# TAM_UNO.net
KiCad netlist of a schematic drawn in EAGLE
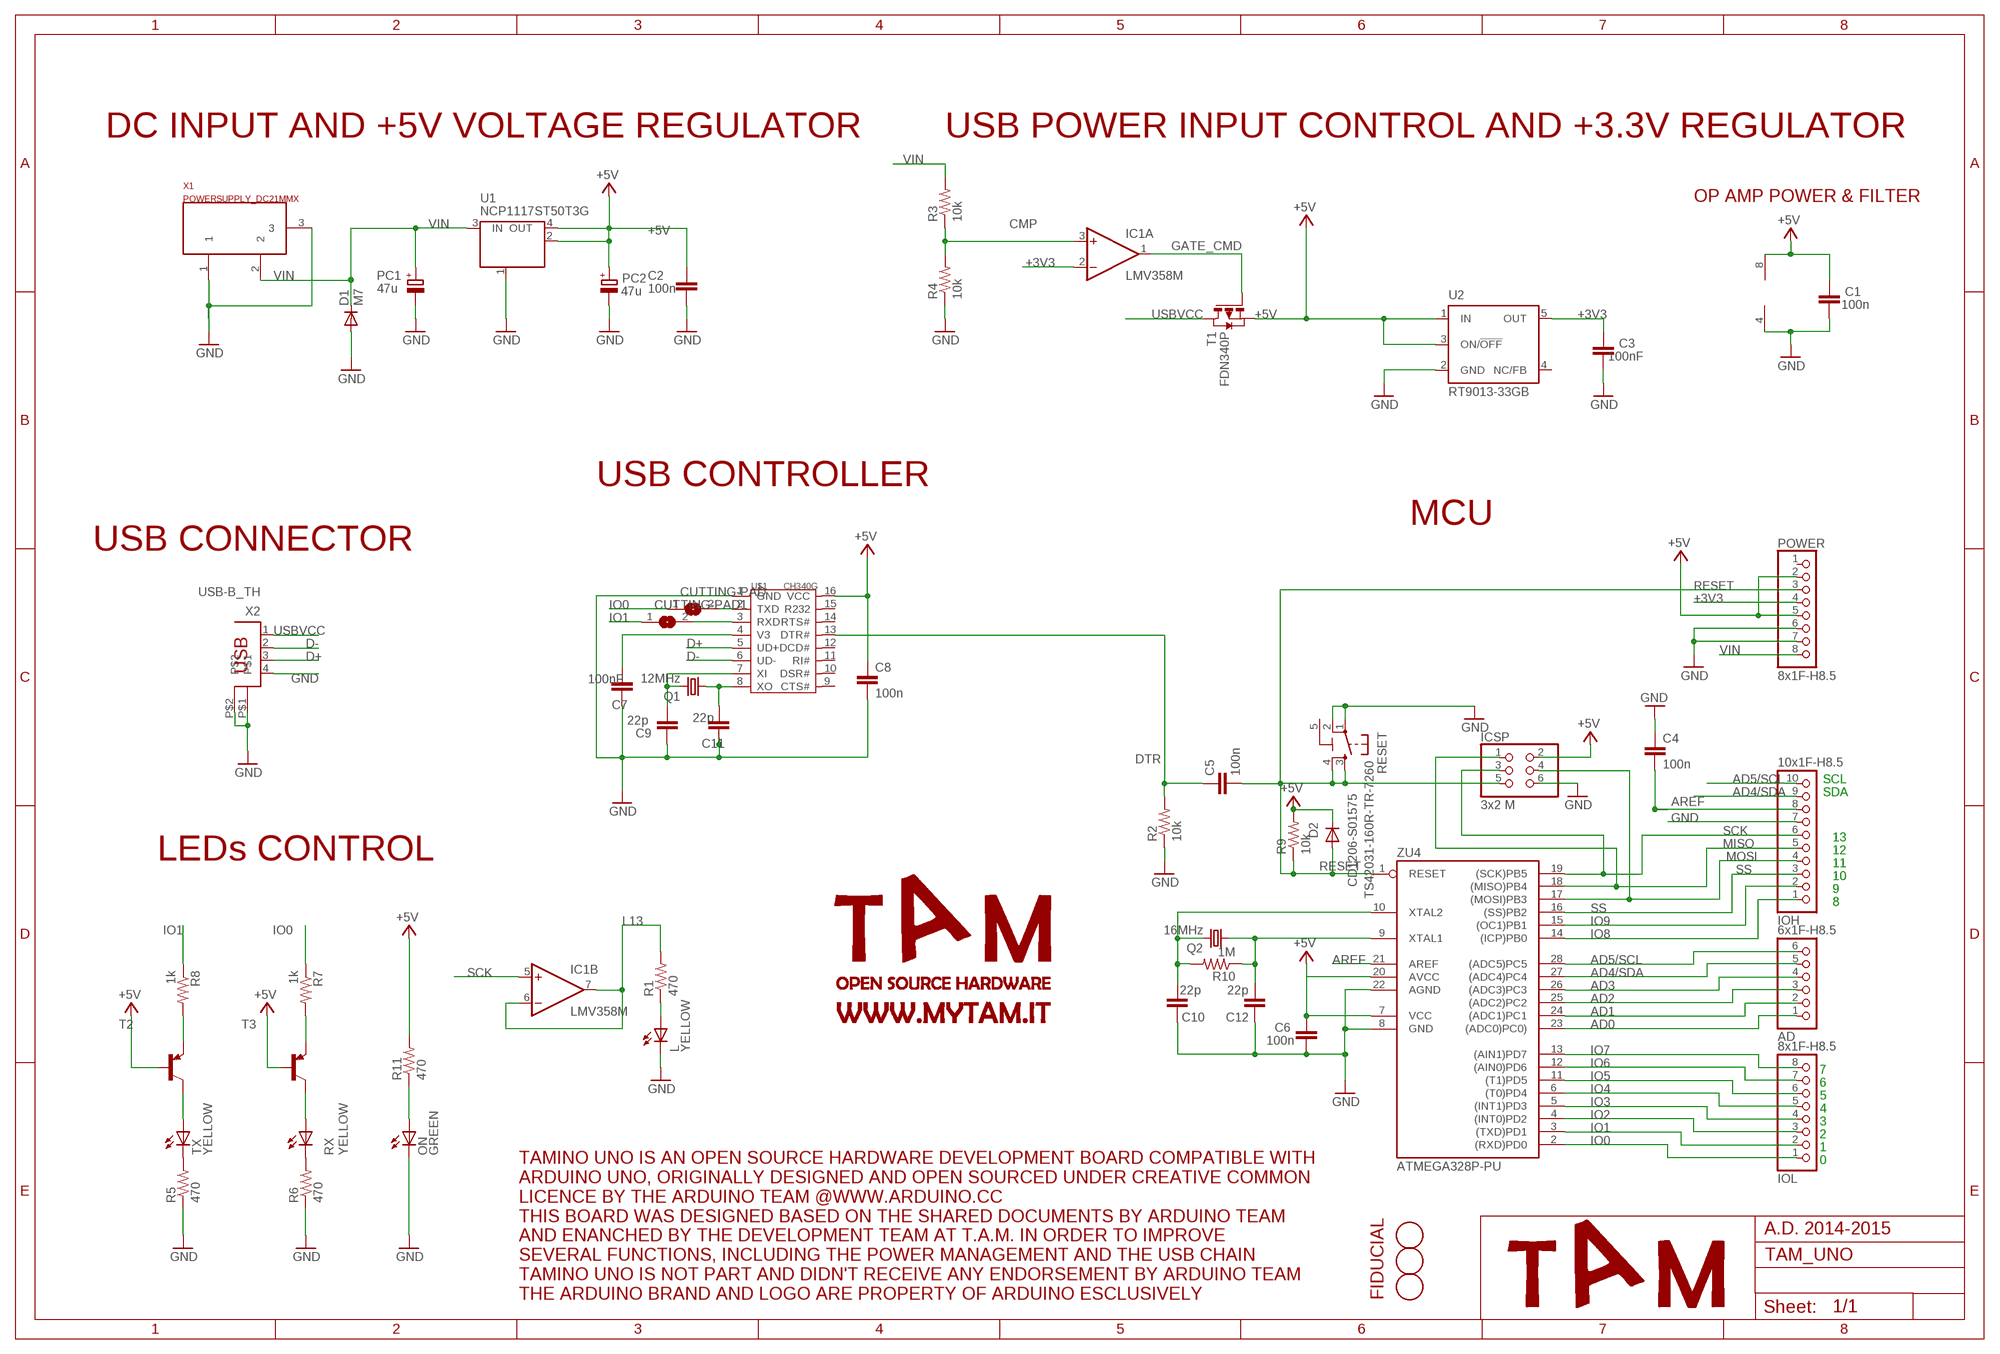
[diagram p0: schematic, sheet 1]

(export (version "E")
  (design (tool "Eeschema 10.0.6"))
  (components
    (comp (ref "AD")
      (value "6x1F-H8.5")
      (footprint "eagle-import:1X06")
      (libsource (lib "eagle-import") (part "PINHD-1X6"))
    )
    (comp (ref "C1")
      (value "100n")
      (footprint "eagle-import:C0603K")
      (libsource (lib "eagle-import") (part "C-EUC0603K"))
    )
    (comp (ref "C2")
      (value "100n")
      (footprint "eagle-import:C0603K")
      (libsource (lib "eagle-import") (part "C-EUC0603K"))
    )
    (comp (ref "C3")
      (value "100nF")
      (footprint "eagle-import:C0603K")
      (libsource (lib "eagle-import") (part "C-EUC0603K"))
    )
    (comp (ref "C4")
      (value "100n")
      (footprint "eagle-import:C0603K")
      (libsource (lib "eagle-import") (part "C-EUC0603K"))
    )
    (comp (ref "C5")
      (value "100n")
      (footprint "eagle-import:C0603K")
      (libsource (lib "eagle-import") (part "C-EUC0603K"))
    )
    (comp (ref "C6")
      (value "100n")
      (footprint "eagle-import:C0603K")
      (libsource (lib "eagle-import") (part "C-EUC0603K"))
    )
    (comp (ref "C7")
      (value "100nF")
      (footprint "eagle-import:C0603K")
      (libsource (lib "eagle-import") (part "C-EUC0603K"))
    )
    (comp (ref "C8")
      (value "100n")
      (footprint "eagle-import:C0603K")
      (libsource (lib "eagle-import") (part "C-EUC0603K"))
    )
    (comp (ref "C9")
      (value "22p")
      (footprint "eagle-import:C0603K")
      (libsource (lib "eagle-import") (part "C-EUC0603K"))
    )
    (comp (ref "C10")
      (value "22p")
      (footprint "eagle-import:C0603K")
      (libsource (lib "eagle-import") (part "C-EUC0603K"))
    )
    (comp (ref "C11")
      (value "22p")
      (footprint "eagle-import:C0603K")
      (libsource (lib "eagle-import") (part "C-EUC0603K"))
    )
    (comp (ref "C12")
      (value "22p")
      (footprint "eagle-import:C0603K")
      (libsource (lib "eagle-import") (part "C-EUC0603K"))
    )
    (comp (ref "CUTTING-PAD")
      (value "SJ")
      (footprint "eagle-import:SJ")
      (libsource (lib "eagle-import") (part "SJ"))
    )
    (comp (ref "CUTTING-PAD1")
      (value "SJ")
      (footprint "eagle-import:SJ")
      (libsource (lib "eagle-import") (part "SJ"))
    )
    (comp (ref "D1")
      (value "M7")
      (footprint "eagle-import:SMB")
      (libsource (lib "eagle-import") (part "DIODE-SMB"))
    )
    (comp (ref "D2")
      (value "CD1206-S01575")
      (footprint "eagle-import:MINIMELF")
      (libsource (lib "eagle-import") (part "DIODE-MINIMELF"))
    )
    (comp (ref "FD1")
      (value "FIDUCIALMOUNT")
      (footprint "eagle-import:FIDUCIA-MOUNT")
      (libsource (lib "eagle-import") (part "FIDUCIALMOUNT"))
    )
    (comp (ref "FD2")
      (value "FIDUCIALMOUNT")
      (footprint "eagle-import:FIDUCIA-MOUNT")
      (libsource (lib "eagle-import") (part "FIDUCIALMOUNT"))
    )
    (comp (ref "FD3")
      (value "FIDUCIALMOUNT")
      (footprint "eagle-import:FIDUCIA-MOUNT")
      (libsource (lib "eagle-import") (part "FIDUCIALMOUNT"))
    )
    (comp (ref "IC1")
      (value "LMV358M")
      (footprint "eagle-import:SO08")
      (libsource (lib "eagle-import") (part "LMV358?M"))
    )
    (comp (ref "ICSP")
      (value "3x2 M")
      (footprint "eagle-import:2X03")
      (libsource (lib "eagle-import") (part "PINHD-2X3"))
    )
    (comp (ref "IOH")
      (value "10x1F-H8.5")
      (footprint "eagle-import:1X10")
      (libsource (lib "eagle-import") (part "PINHD-1X10_ARD"))
    )
    (comp (ref "IOL")
      (value "8x1F-H8.5")
      (footprint "eagle-import:1X08")
      (libsource (lib "eagle-import") (part "PINHD-1X8"))
    )
    (comp (ref "L")
      (value "YELLOW")
      (footprint "eagle-import:CHIP-LED0805")
      (libsource (lib "eagle-import") (part "LEDCHIP-LED0805"))
    )
    (comp (ref "ON")
      (value "GREEN")
      (footprint "eagle-import:CHIP-LED0805")
      (libsource (lib "eagle-import") (part "LEDCHIP-LED0805"))
    )
    (comp (ref "PC1")
      (value "47u")
      (footprint "eagle-import:PANASONIC_D")
      (libsource (lib "eagle-import") (part "CPOL-EUD"))
    )
    (comp (ref "PC2")
      (value "47u")
      (footprint "eagle-import:PANASONIC_D")
      (libsource (lib "eagle-import") (part "CPOL-EUD"))
    )
    (comp (ref "POWER")
      (value "8x1F-H8.5")
      (footprint "eagle-import:1X08")
      (libsource (lib "eagle-import") (part "PINHD-1X8"))
    )
    (comp (ref "Q1")
      (value "12MHz")
      (footprint "eagle-import:SM49")
      (libsource (lib "eagle-import") (part "CRYSTALSM49"))
    )
    (comp (ref "Q2")
      (value "16MHz")
      (footprint "eagle-import:SM49")
      (libsource (lib "eagle-import") (part "CRYSTALSM49"))
    )
    (comp (ref "R1")
      (value "470")
      (footprint "eagle-import:R0603")
      (libsource (lib "eagle-import") (part "R-US_R0603"))
    )
    (comp (ref "R2")
      (value "10k")
      (footprint "eagle-import:R0603")
      (libsource (lib "eagle-import") (part "R-US_R0603"))
    )
    (comp (ref "R3")
      (value "10k")
      (footprint "eagle-import:R0603")
      (libsource (lib "eagle-import") (part "R-US_R0603"))
    )
    (comp (ref "R4")
      (value "10k")
      (footprint "eagle-import:R0603")
      (libsource (lib "eagle-import") (part "R-US_R0603"))
    )
    (comp (ref "R5")
      (value "470")
      (footprint "eagle-import:R0603")
      (libsource (lib "eagle-import") (part "R-US_R0603"))
    )
    (comp (ref "R6")
      (value "470")
      (footprint "eagle-import:R0603")
      (libsource (lib "eagle-import") (part "R-US_R0603"))
    )
    (comp (ref "R7")
      (value "1k")
      (footprint "eagle-import:R0603")
      (libsource (lib "eagle-import") (part "R-US_R0603"))
    )
    (comp (ref "R8")
      (value "1k")
      (footprint "eagle-import:R0603")
      (libsource (lib "eagle-import") (part "R-US_R0603"))
    )
    (comp (ref "R9")
      (value "10k")
      (footprint "eagle-import:R0603")
      (libsource (lib "eagle-import") (part "R-US_R0603"))
    )
    (comp (ref "R10")
      (value "1M")
      (footprint "eagle-import:R0603")
      (libsource (lib "eagle-import") (part "R-US_R0603"))
    )
    (comp (ref "R11")
      (value "470")
      (footprint "eagle-import:R0603")
      (libsource (lib "eagle-import") (part "R-US_R0603"))
    )
    (comp (ref "RESET")
      (value "TS42031-160R-TR-7260")
      (footprint "eagle-import:TS42")
      (libsource (lib "eagle-import") (part "TS42"))
    )
    (comp (ref "RX")
      (value "YELLOW")
      (footprint "eagle-import:CHIP-LED0805")
      (libsource (lib "eagle-import") (part "LEDCHIP-LED0805"))
    )
    (comp (ref "T1")
      (value "FDN340P")
      (footprint "eagle-import:SOT-23")
      (libsource (lib "eagle-import") (part "PMOSSOT23"))
    )
    (comp (ref "T2")
      (value "-PNP-SOT23-EBC")
      (footprint "eagle-import:SOT23-EBC")
      (libsource (lib "eagle-import") (part "-PNP-SOT23-EBC"))
    )
    (comp (ref "T3")
      (value "-PNP-SOT23-EBC")
      (footprint "eagle-import:SOT23-EBC")
      (libsource (lib "eagle-import") (part "-PNP-SOT23-EBC"))
    )
    (comp (ref "TX")
      (value "YELLOW")
      (footprint "eagle-import:CHIP-LED0805")
      (libsource (lib "eagle-import") (part "LEDCHIP-LED0805"))
    )
    (comp (ref "U$1")
      (value "CH340G")
      (footprint "eagle-import:SSOP16")
      (libsource (lib "eagle-import") (part "CH340GALT"))
    )
    (comp (ref "U1")
      (value "NCP1117ST50T3G")
      (footprint "eagle-import:SOT223")
      (libsource (lib "eagle-import") (part "MC33269ST-3.3T3"))
    )
    (comp (ref "U2")
      (value "RT9013-33GB")
      (footprint "eagle-import:SOT23-DBV")
      (libsource (lib "eagle-import") (part "LP2985-XXDBVR33"))
    )
    (comp (ref "X1")
      (value "POWERSUPPLY_DC21MMX")
      (footprint "eagle-import:POWERSUPPLY_DC-21MM")
      (libsource (lib "eagle-import") (part "POWERSUPPLY_DC21MMX"))
    )
    (comp (ref "X2")
      (value "USB-B_TH")
      (footprint "eagle-import:PN61729")
      (libsource (lib "eagle-import") (part "PN61729"))
    )
    (comp (ref "ZU4")
      (value "ATMEGA328P-PU")
      (footprint "eagle-import:DIL28-3")
      (libsource (lib "eagle-import") (part "ATMEGA328P-PU"))
    )
  )
  (nets
    (net (code "1") (name "+5V") (class "Default")
      (node (ref "C1") (pin "2") (pinfunction "2_2") (pintype "passive"))
      (node (ref "C2") (pin "2") (pinfunction "2_2") (pintype "passive"))
      (node (ref "C6") (pin "2") (pinfunction "2_2") (pintype "passive"))
      (node (ref "C8") (pin "1") (pinfunction "1_1") (pintype "passive"))
      (node (ref "D2") (pin "C") (pinfunction "C_C") (pintype "passive"))
      (node (ref "IC1") (pin "8") (pinfunction "V+_8") (pintype "power_in"))
      (node (ref "ICSP") (pin "2") (pinfunction "2_2") (pintype "passive"))
      (node (ref "PC2") (pin "+") (pinfunction "+_+") (pintype "passive"))
      (node (ref "POWER") (pin "2") (pinfunction "2_2") (pintype "passive"))
      (node (ref "POWER") (pin "5") (pinfunction "5_5") (pintype "passive"))
      (node (ref "R11") (pin "2") (pinfunction "2_2") (pintype "passive"))
      (node (ref "R9") (pin "2") (pinfunction "2_2") (pintype "passive"))
      (node (ref "T1") (pin "2") (pinfunction "S_2") (pintype "passive"))
      (node (ref "T2") (pin "B") (pinfunction "B_B") (pintype "passive"))
      (node (ref "T3") (pin "B") (pinfunction "B_B") (pintype "passive"))
      (node (ref "U$1") (pin "16") (pinfunction "VCC_16") (pintype "power_in"))
      (node (ref "U1") (pin "2") (pinfunction "OUT_2") (pintype "passive"))
      (node (ref "U1") (pin "4") (pinfunction "OUT_4") (pintype "passive"))
      (node (ref "U2") (pin "1") (pinfunction "IN_1") (pintype "input"))
      (node (ref "U2") (pin "3") (pinfunction "ON/~{OFF}_3") (pintype "input"))
      (node (ref "ZU4") (pin "20") (pinfunction "AVCC_20") (pintype "power_in"))
      (node (ref "ZU4") (pin "7") (pinfunction "VCC_7") (pintype "power_in"))
    )
    (net (code "2") (name "/+3V3") (class "Default")
      (node (ref "C3") (pin "2") (pinfunction "2_2") (pintype "passive"))
      (node (ref "IC1") (pin "2") (pinfunction "-IN_2") (pintype "input"))
      (node (ref "POWER") (pin "4") (pinfunction "4_4") (pintype "passive"))
      (node (ref "U2") (pin "5") (pinfunction "OUT_5") (pintype "passive"))
    )
    (net (code "3") (name "/5-GND") (class "Default")
      (node (ref "RESET") (pin "5") (pinfunction "5-GND_5") (pintype "power_in"))
    )
    (net (code "4") (name "/AD0") (class "Default")
      (node (ref "AD") (pin "1") (pinfunction "1_1") (pintype "passive"))
      (node (ref "ZU4") (pin "23") (pinfunction "(ADC0)PC0)_23") (pintype "bidirectional"))
    )
    (net (code "5") (name "/AD1") (class "Default")
      (node (ref "AD") (pin "2") (pinfunction "2_2") (pintype "passive"))
      (node (ref "ZU4") (pin "24") (pinfunction "(ADC1)PC1_24") (pintype "bidirectional"))
    )
    (net (code "6") (name "/AD2") (class "Default")
      (node (ref "AD") (pin "3") (pinfunction "3_3") (pintype "passive"))
      (node (ref "ZU4") (pin "25") (pinfunction "(ADC2)PC2_25") (pintype "bidirectional"))
    )
    (net (code "7") (name "/AD3") (class "Default")
      (node (ref "AD") (pin "4") (pinfunction "4_4") (pintype "passive"))
      (node (ref "ZU4") (pin "26") (pinfunction "(ADC3)PC3_26") (pintype "bidirectional"))
    )
    (net (code "8") (name "/AD4{slash}SDA") (class "Default")
      (node (ref "AD") (pin "5") (pinfunction "5_5") (pintype "passive"))
      (node (ref "IOH") (pin "9") (pinfunction "9_9") (pintype "passive"))
      (node (ref "ZU4") (pin "27") (pinfunction "(ADC4)PC4_27") (pintype "bidirectional"))
    )
    (net (code "9") (name "/AD5{slash}SCL") (class "Default")
      (node (ref "AD") (pin "6") (pinfunction "6_6") (pintype "passive"))
      (node (ref "IOH") (pin "10") (pinfunction "10_10") (pintype "passive"))
      (node (ref "ZU4") (pin "28") (pinfunction "(ADC5)PC5_28") (pintype "bidirectional"))
    )
    (net (code "10") (name "/AREF") (class "Default")
      (node (ref "C4") (pin "2") (pinfunction "2_2") (pintype "passive"))
      (node (ref "IOH") (pin "8") (pinfunction "8_8") (pintype "passive"))
      (node (ref "ZU4") (pin "21") (pinfunction "AREF_21") (pintype "passive"))
    )
    (net (code "11") (name "/CMP") (class "Default")
      (node (ref "IC1") (pin "3") (pinfunction "+IN_3") (pintype "input"))
      (node (ref "R3") (pin "1") (pinfunction "1_1") (pintype "passive"))
      (node (ref "R4") (pin "2") (pinfunction "2_2") (pintype "passive"))
    )
    (net (code "12") (name "/D+") (class "Default")
      (node (ref "U$1") (pin "5") (pinfunction "UD+_5") (pintype "bidirectional"))
      (node (ref "X2") (pin "3") (pinfunction "3_3") (pintype "bidirectional"))
    )
    (net (code "13") (name "/D-") (class "Default")
      (node (ref "U$1") (pin "6") (pinfunction "UD-_6") (pintype "bidirectional"))
      (node (ref "X2") (pin "2") (pinfunction "2_2") (pintype "bidirectional"))
    )
    (net (code "14") (name "/DTR") (class "Default")
      (node (ref "C5") (pin "1") (pinfunction "1_1") (pintype "passive"))
      (node (ref "R2") (pin "2") (pinfunction "2_2") (pintype "passive"))
      (node (ref "U$1") (pin "13") (pinfunction "DTR#_13") (pintype "output"))
    )
    (net (code "15") (name "/GATE_CMD") (class "Default")
      (node (ref "IC1") (pin "1") (pinfunction "OUT_1") (pintype "output"))
      (node (ref "T1") (pin "3") (pinfunction "G_3") (pintype "passive"))
    )
    (net (code "16") (name "/IO0") (class "Default")
      (node (ref "CUTTING-PAD") (pin "1") (pinfunction "1_1") (pintype "passive"))
      (node (ref "IOL") (pin "1") (pinfunction "1_1") (pintype "passive"))
      (node (ref "R7") (pin "1") (pinfunction "1_1") (pintype "passive"))
      (node (ref "ZU4") (pin "2") (pinfunction "(RXD)PD0_2") (pintype "bidirectional"))
    )
    (net (code "17") (name "/IO1") (class "Default")
      (node (ref "CUTTING-PAD1") (pin "1") (pinfunction "1_1") (pintype "passive"))
      (node (ref "IOL") (pin "2") (pinfunction "2_2") (pintype "passive"))
      (node (ref "R8") (pin "1") (pinfunction "1_1") (pintype "passive"))
      (node (ref "ZU4") (pin "3") (pinfunction "(TXD)PD1_3") (pintype "bidirectional"))
    )
    (net (code "18") (name "/IO2") (class "Default")
      (node (ref "IOL") (pin "3") (pinfunction "3_3") (pintype "passive"))
      (node (ref "ZU4") (pin "4") (pinfunction "(INT0)PD2_4") (pintype "bidirectional"))
    )
    (net (code "19") (name "/IO3") (class "Default")
      (node (ref "IOL") (pin "4") (pinfunction "4_4") (pintype "passive"))
      (node (ref "ZU4") (pin "5") (pinfunction "(INT1)PD3_5") (pintype "bidirectional"))
    )
    (net (code "20") (name "/IO4") (class "Default")
      (node (ref "IOL") (pin "5") (pinfunction "5_5") (pintype "passive"))
      (node (ref "ZU4") (pin "6") (pinfunction "(T0)PD4_6") (pintype "bidirectional"))
    )
    (net (code "21") (name "/IO5") (class "Default")
      (node (ref "IOL") (pin "6") (pinfunction "6_6") (pintype "passive"))
      (node (ref "ZU4") (pin "11") (pinfunction "(T1)PD5_11") (pintype "bidirectional"))
    )
    (net (code "22") (name "/IO6") (class "Default")
      (node (ref "IOL") (pin "7") (pinfunction "7_7") (pintype "passive"))
      (node (ref "ZU4") (pin "12") (pinfunction "(AIN0)PD6_12") (pintype "bidirectional"))
    )
    (net (code "23") (name "/IO7") (class "Default")
      (node (ref "IOL") (pin "8") (pinfunction "8_8") (pintype "passive"))
      (node (ref "ZU4") (pin "13") (pinfunction "(AIN1)PD7_13") (pintype "bidirectional"))
    )
    (net (code "24") (name "/IO8") (class "Default")
      (node (ref "IOH") (pin "1") (pinfunction "1_1") (pintype "passive"))
      (node (ref "ZU4") (pin "14") (pinfunction "(ICP)PB0_14") (pintype "bidirectional"))
    )
    (net (code "25") (name "/IO9") (class "Default")
      (node (ref "IOH") (pin "2") (pinfunction "2_2") (pintype "passive"))
      (node (ref "ZU4") (pin "15") (pinfunction "(OC1)PB1_15") (pintype "bidirectional"))
    )
    (net (code "26") (name "/L13") (class "Default")
      (node (ref "IC1") (pin "6") (pinfunction "-IN_6") (pintype "input"))
      (node (ref "IC1") (pin "7") (pinfunction "OUT_7") (pintype "output"))
      (node (ref "R1") (pin "2") (pinfunction "2_2") (pintype "passive"))
    )
    (net (code "27") (name "/MISO") (class "Default")
      (node (ref "ICSP") (pin "1") (pinfunction "1_1") (pintype "passive"))
      (node (ref "IOH") (pin "5") (pinfunction "5_5") (pintype "passive"))
      (node (ref "ZU4") (pin "18") (pinfunction "(MISO)PB4_18") (pintype "bidirectional"))
    )
    (net (code "28") (name "/MOSI") (class "Default")
      (node (ref "ICSP") (pin "4") (pinfunction "4_4") (pintype "passive"))
      (node (ref "IOH") (pin "4") (pinfunction "4_4") (pintype "passive"))
      (node (ref "ZU4") (pin "17") (pinfunction "(MOSI)PB3_17") (pintype "bidirectional"))
    )
    (net (code "29") (name "/RESET") (class "Default")
      (node (ref "C5") (pin "2") (pinfunction "2_2") (pintype "passive"))
      (node (ref "D2") (pin "A") (pinfunction "A_A") (pintype "passive"))
      (node (ref "ICSP") (pin "5") (pinfunction "5_5") (pintype "passive"))
      (node (ref "POWER") (pin "3") (pinfunction "3_3") (pintype "passive"))
      (node (ref "R9") (pin "1") (pinfunction "1_1") (pintype "passive"))
      (node (ref "RESET") (pin "3") (pinfunction "3_3") (pintype "passive"))
      (node (ref "RESET") (pin "4") (pinfunction "4_4") (pintype "passive"))
      (node (ref "ZU4") (pin "1") (pinfunction "RESET_1") (pintype "input"))
    )
    (net (code "30") (name "/SCK") (class "Default")
      (node (ref "IC1") (pin "5") (pinfunction "+IN_5") (pintype "input"))
      (node (ref "ICSP") (pin "3") (pinfunction "3_3") (pintype "passive"))
      (node (ref "IOH") (pin "6") (pinfunction "6_6") (pintype "passive"))
      (node (ref "ZU4") (pin "19") (pinfunction "(SCK)PB5_19") (pintype "bidirectional"))
    )
    (net (code "31") (name "/SS") (class "Default")
      (node (ref "IOH") (pin "3") (pinfunction "3_3") (pintype "passive"))
      (node (ref "ZU4") (pin "16") (pinfunction "(SS)PB2_16") (pintype "bidirectional"))
    )
    (net (code "32") (name "/USBVCC") (class "Default")
      (node (ref "T1") (pin "1") (pinfunction "D_1") (pintype "passive"))
      (node (ref "X2") (pin "1") (pinfunction "1_1") (pintype "bidirectional"))
    )
    (net (code "33") (name "/VIN") (class "Default")
      (node (ref "D1") (pin "C") (pinfunction "C_C") (pintype "passive"))
      (node (ref "PC1") (pin "+") (pinfunction "+_+") (pintype "passive"))
      (node (ref "POWER") (pin "8") (pinfunction "8_8") (pintype "passive"))
      (node (ref "R3") (pin "2") (pinfunction "2_2") (pintype "passive"))
      (node (ref "U1") (pin "3") (pinfunction "IN_3") (pintype "input"))
      (node (ref "X1") (pin "2") (pinfunction "2_2") (pintype "power_in"))
    )
    (net (code "34") (name "GND") (class "Default")
      (node (ref "C1") (pin "1") (pinfunction "1_1") (pintype "passive"))
      (node (ref "C10") (pin "2") (pinfunction "2_2") (pintype "passive"))
      (node (ref "C11") (pin "2") (pinfunction "2_2") (pintype "passive"))
      (node (ref "C12") (pin "2") (pinfunction "2_2") (pintype "passive"))
      (node (ref "C2") (pin "1") (pinfunction "1_1") (pintype "passive"))
      (node (ref "C3") (pin "1") (pinfunction "1_1") (pintype "passive"))
      (node (ref "C4") (pin "1") (pinfunction "1_1") (pintype "passive"))
      (node (ref "C6") (pin "1") (pinfunction "1_1") (pintype "passive"))
      (node (ref "C7") (pin "2") (pinfunction "2_2") (pintype "passive"))
      (node (ref "C8") (pin "2") (pinfunction "2_2") (pintype "passive"))
      (node (ref "C9") (pin "2") (pinfunction "2_2") (pintype "passive"))
      (node (ref "D1") (pin "A") (pinfunction "A_A") (pintype "passive"))
      (node (ref "IC1") (pin "4") (pinfunction "V-_4") (pintype "power_in"))
      (node (ref "ICSP") (pin "6") (pinfunction "6_6") (pintype "passive"))
      (node (ref "IOH") (pin "7") (pinfunction "7_7") (pintype "passive"))
      (node (ref "L") (pin "C") (pinfunction "C_C") (pintype "passive"))
      (node (ref "ON") (pin "C") (pinfunction "C_C") (pintype "passive"))
      (node (ref "PC1") (pin "-") (pinfunction "-_-") (pintype "passive"))
      (node (ref "PC2") (pin "-") (pinfunction "-_-") (pintype "passive"))
      (node (ref "POWER") (pin "6") (pinfunction "6_6") (pintype "passive"))
      (node (ref "POWER") (pin "7") (pinfunction "7_7") (pintype "passive"))
      (node (ref "R2") (pin "1") (pinfunction "1_1") (pintype "passive"))
      (node (ref "R4") (pin "1") (pinfunction "1_1") (pintype "passive"))
      (node (ref "R5") (pin "1") (pinfunction "1_1") (pintype "passive"))
      (node (ref "R6") (pin "1") (pinfunction "1_1") (pintype "passive"))
      (node (ref "RESET") (pin "1") (pinfunction "1_1") (pintype "passive"))
      (node (ref "RESET") (pin "2") (pinfunction "2_2") (pintype "passive"))
      (node (ref "U$1") (pin "1") (pinfunction "GND_1") (pintype "power_in"))
      (node (ref "U1") (pin "1") (pinfunction "GND/ADJ_1") (pintype "input"))
      (node (ref "U2") (pin "2") (pinfunction "GND_2") (pintype "power_in"))
      (node (ref "X1") (pin "1") (pinfunction "1_1") (pintype "power_in"))
      (node (ref "X1") (pin "3") (pinfunction "3_3") (pintype "power_in"))
      (node (ref "X2") (pin "4") (pinfunction "4_4") (pintype "bidirectional"))
      (node (ref "X2") (pin "P$1") (pinfunction "P$1_P$1") (pintype "bidirectional"))
      (node (ref "X2") (pin "P$2") (pinfunction "P$2_P$2") (pintype "bidirectional"))
      (node (ref "ZU4") (pin "22") (pinfunction "AGND_22") (pintype "power_in"))
      (node (ref "ZU4") (pin "8") (pinfunction "GND_8") (pintype "power_in"))
    )
    (net (code "35") (name "Net-(L-PadA)") (class "Default")
      (node (ref "L") (pin "A") (pinfunction "A_A") (pintype "passive"))
      (node (ref "R1") (pin "1") (pinfunction "1_1") (pintype "passive"))
    )
    (net (code "36") (name "Net-(ON-PadA)") (class "Default")
      (node (ref "ON") (pin "A") (pinfunction "A_A") (pintype "passive"))
      (node (ref "R11") (pin "1") (pinfunction "1_1") (pintype "passive"))
    )
    (net (code "37") (name "Net-(R5-Pad2)") (class "Default")
      (node (ref "R5") (pin "2") (pinfunction "2_2") (pintype "passive"))
      (node (ref "TX") (pin "C") (pinfunction "C_C") (pintype "passive"))
    )
    (net (code "38") (name "Net-(R6-Pad2)") (class "Default")
      (node (ref "R6") (pin "2") (pinfunction "2_2") (pintype "passive"))
      (node (ref "RX") (pin "C") (pinfunction "C_C") (pintype "passive"))
    )
    (net (code "39") (name "Net-(R7-Pad2)") (class "Default")
      (node (ref "R7") (pin "2") (pinfunction "2_2") (pintype "passive"))
      (node (ref "T3") (pin "E") (pinfunction "E_E") (pintype "passive"))
    )
    (net (code "40") (name "Net-(R8-Pad2)") (class "Default")
      (node (ref "R8") (pin "2") (pinfunction "2_2") (pintype "passive"))
      (node (ref "T2") (pin "E") (pinfunction "E_E") (pintype "passive"))
    )
    (net (code "41") (name "Net-(RX-PadA)") (class "Default")
      (node (ref "RX") (pin "A") (pinfunction "A_A") (pintype "passive"))
      (node (ref "T3") (pin "C") (pinfunction "C_C") (pintype "passive"))
    )
    (net (code "42") (name "Net-(T2-PadC)") (class "Default")
      (node (ref "T2") (pin "C") (pinfunction "C_C") (pintype "passive"))
      (node (ref "TX") (pin "A") (pinfunction "A_A") (pintype "passive"))
    )
    (net (code "43") (name "Net-(U$1-RXD)") (class "Default")
      (node (ref "CUTTING-PAD1") (pin "2") (pinfunction "2_2") (pintype "passive"))
      (node (ref "U$1") (pin "3") (pinfunction "RXD_3") (pintype "input"))
    )
    (net (code "44") (name "Net-(U$1-TXD)") (class "Default")
      (node (ref "CUTTING-PAD") (pin "2") (pinfunction "2_2") (pintype "passive"))
      (node (ref "U$1") (pin "2") (pinfunction "TXD_2") (pintype "output"))
    )
    (net (code "45") (name "Net-(U$1-V3)") (class "Default")
      (node (ref "C7") (pin "1") (pinfunction "1_1") (pintype "passive"))
      (node (ref "U$1") (pin "4") (pinfunction "V3_4") (pintype "power_in"))
    )
    (net (code "46") (name "Net-(U$1-XI)") (class "Default")
      (node (ref "C9") (pin "1") (pinfunction "1_1") (pintype "passive"))
      (node (ref "Q1") (pin "2") (pinfunction "2_2") (pintype "passive"))
      (node (ref "U$1") (pin "7") (pinfunction "XI_7") (pintype "input"))
    )
    (net (code "47") (name "Net-(U$1-XO)") (class "Default")
      (node (ref "C11") (pin "1") (pinfunction "1_1") (pintype "passive"))
      (node (ref "Q1") (pin "1") (pinfunction "1_1") (pintype "passive"))
      (node (ref "U$1") (pin "8") (pinfunction "XO_8") (pintype "output"))
    )
    (net (code "48") (name "Net-(ZU4-XTAL1)") (class "Default")
      (node (ref "C12") (pin "1") (pinfunction "1_1") (pintype "passive"))
      (node (ref "Q2") (pin "1") (pinfunction "1_1") (pintype "passive"))
      (node (ref "R10") (pin "1") (pinfunction "1_1") (pintype "passive"))
      (node (ref "ZU4") (pin "9") (pinfunction "XTAL1_9") (pintype "bidirectional"))
    )
    (net (code "49") (name "Net-(ZU4-XTAL2)") (class "Default")
      (node (ref "C10") (pin "1") (pinfunction "1_1") (pintype "passive"))
      (node (ref "Q2") (pin "2") (pinfunction "2_2") (pintype "passive"))
      (node (ref "R10") (pin "2") (pinfunction "2_2") (pintype "passive"))
      (node (ref "ZU4") (pin "10") (pinfunction "XTAL2_10") (pintype "bidirectional"))
    )
    (net (code "50") (name "unconnected-(POWER-Pad1)") (class "Default")
      (node (ref "POWER") (pin "1") (pinfunction "1_1") (pintype "passive"))
    )
    (net (code "51") (name "unconnected-(U$1-CTS#-Pad9)") (class "Default")
      (node (ref "U$1") (pin "9") (pinfunction "CTS#_9") (pintype "input"))
    )
    (net (code "52") (name "unconnected-(U$1-DCD#-Pad12)") (class "Default")
      (node (ref "U$1") (pin "12") (pinfunction "DCD#_12") (pintype "input"))
    )
    (net (code "53") (name "unconnected-(U$1-DSR#-Pad10)") (class "Default")
      (node (ref "U$1") (pin "10") (pinfunction "DSR#_10") (pintype "input"))
    )
    (net (code "54") (name "unconnected-(U$1-R232-Pad15)") (class "Default")
      (node (ref "U$1") (pin "15") (pinfunction "R232_15") (pintype "input"))
    )
    (net (code "55") (name "unconnected-(U$1-RI#-Pad11)") (class "Default")
      (node (ref "U$1") (pin "11") (pinfunction "RI#_11") (pintype "input"))
    )
    (net (code "56") (name "unconnected-(U$1-RTS#-Pad14)") (class "Default")
      (node (ref "U$1") (pin "14") (pinfunction "RTS#_14") (pintype "output"))
    )
    (net (code "57") (name "unconnected-(U2-NC{slash}FB-Pad4)") (class "Default")
      (node (ref "U2") (pin "4") (pinfunction "NC/FB_4") (pintype "passive"))
    )
  )
)
